# R401F.net
KiCad netlist of a schematic drawn in EAGLE
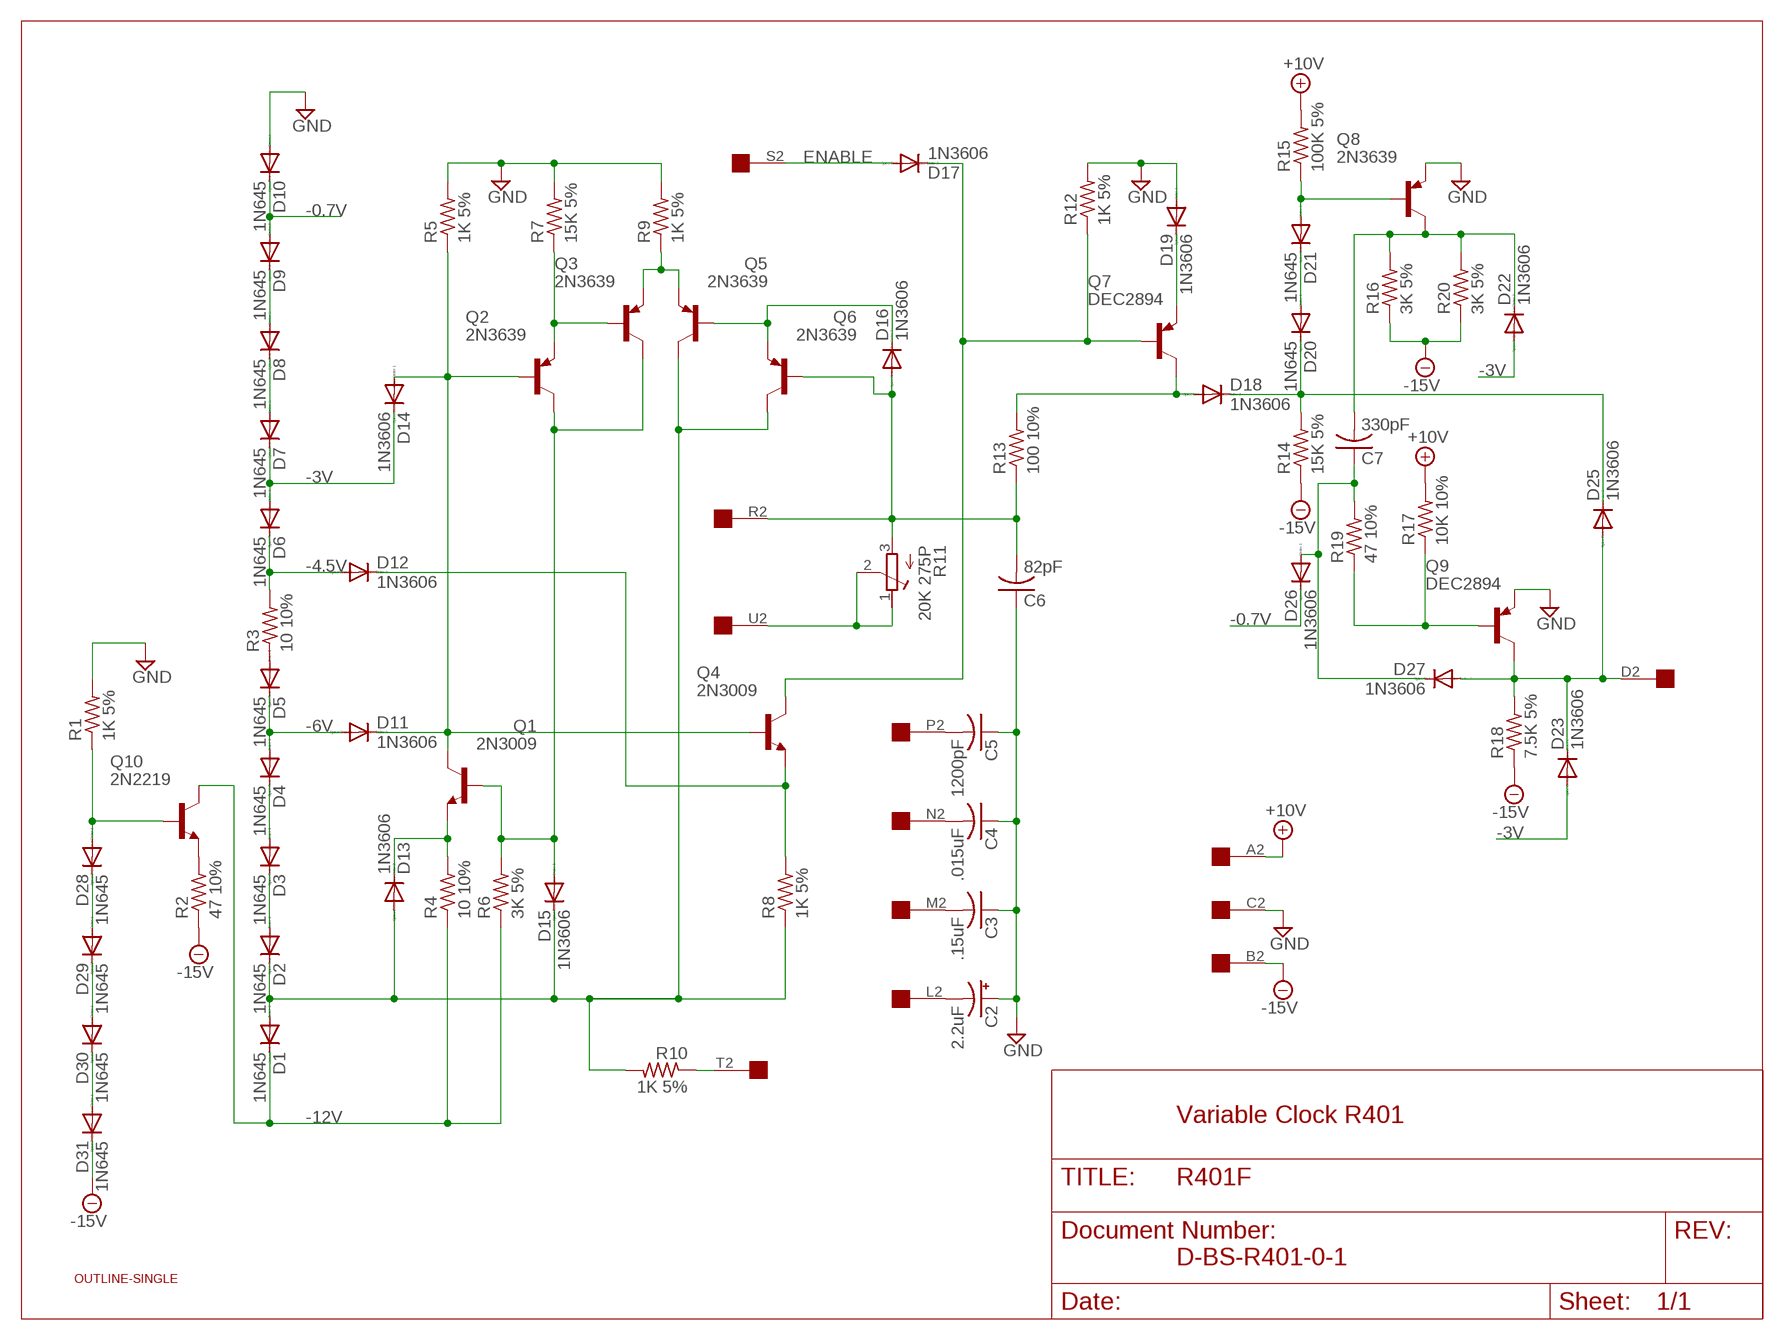
[diagram p0: schematic, sheet 1]

(export (version "E")
  (design (tool "Eeschema 10.0.6"))
  (components
    (comp (ref "C2")
      (value "2.2uF")
      (footprint "eagle-import:E12-4")
      (libsource (lib "eagle-import") (part "CPOL-USE12-4AXIAL"))
    )
    (comp (ref "C3")
      (value ".15uF")
      (footprint "eagle-import:C275-093X316")
      (libsource (lib "eagle-import") (part "C-US275-093X316"))
    )
    (comp (ref "C4")
      (value ".015uF")
      (footprint "eagle-import:C150-054X183")
      (libsource (lib "eagle-import") (part "C-US150-054X183"))
    )
    (comp (ref "C5")
      (value "1200pF")
      (footprint "eagle-import:C102-043X133")
      (libsource (lib "eagle-import") (part "C-US102-043X133"))
    )
    (comp (ref "C6")
      (value "82pF")
      (footprint "eagle-import:C150-054X183")
      (libsource (lib "eagle-import") (part "C-US150-054X183"))
    )
    (comp (ref "C7")
      (value "330pF")
      (footprint "eagle-import:C150-054X183")
      (libsource (lib "eagle-import") (part "C-US150-054X183"))
    )
    (comp (ref "D1")
      (value "1N645")
      (footprint "eagle-import:DO35-10")
      (libsource (lib "eagle-import") (part "1N4148DO35-10"))
    )
    (comp (ref "D2")
      (value "1N645")
      (footprint "eagle-import:DO35-10")
      (libsource (lib "eagle-import") (part "1N4148DO35-10"))
    )
    (comp (ref "D3")
      (value "1N645")
      (footprint "eagle-import:DO35-10")
      (libsource (lib "eagle-import") (part "1N4148DO35-10"))
    )
    (comp (ref "D4")
      (value "1N645")
      (footprint "eagle-import:DO35-10")
      (libsource (lib "eagle-import") (part "1N4148DO35-10"))
    )
    (comp (ref "D5")
      (value "1N645")
      (footprint "eagle-import:DO35-10")
      (libsource (lib "eagle-import") (part "1N4148DO35-10"))
    )
    (comp (ref "D6")
      (value "1N645")
      (footprint "eagle-import:DO35-10")
      (libsource (lib "eagle-import") (part "1N4148DO35-10"))
    )
    (comp (ref "D7")
      (value "1N645")
      (footprint "eagle-import:DO35-10")
      (libsource (lib "eagle-import") (part "1N4148DO35-10"))
    )
    (comp (ref "D8")
      (value "1N645")
      (footprint "eagle-import:DO35-10")
      (libsource (lib "eagle-import") (part "1N4148DO35-10"))
    )
    (comp (ref "D9")
      (value "1N645")
      (footprint "eagle-import:DO35-10")
      (libsource (lib "eagle-import") (part "1N4148DO35-10"))
    )
    (comp (ref "D10")
      (value "1N645")
      (footprint "eagle-import:DO35-10")
      (libsource (lib "eagle-import") (part "1N4148DO35-10"))
    )
    (comp (ref "D11")
      (value "1N3606")
      (footprint "eagle-import:DO35-10")
      (libsource (lib "eagle-import") (part "1N4148DO35-10"))
    )
    (comp (ref "D12")
      (value "1N3606")
      (footprint "eagle-import:DO35-10")
      (libsource (lib "eagle-import") (part "1N4148DO35-10"))
    )
    (comp (ref "D13")
      (value "1N3606")
      (footprint "eagle-import:DO35-10")
      (libsource (lib "eagle-import") (part "1N4148DO35-10"))
    )
    (comp (ref "D14")
      (value "1N3606")
      (footprint "eagle-import:DO35-10")
      (libsource (lib "eagle-import") (part "1N4148DO35-10"))
    )
    (comp (ref "D15")
      (value "1N3606")
      (footprint "eagle-import:DO35-10")
      (libsource (lib "eagle-import") (part "1N4148DO35-10"))
    )
    (comp (ref "D16")
      (value "1N3606")
      (footprint "eagle-import:DO35-10")
      (libsource (lib "eagle-import") (part "1N4148DO35-10"))
    )
    (comp (ref "D17")
      (value "1N3606")
      (footprint "eagle-import:DO35-10")
      (libsource (lib "eagle-import") (part "1N4148DO35-10"))
    )
    (comp (ref "D18")
      (value "1N3606")
      (footprint "eagle-import:DO35-10")
      (libsource (lib "eagle-import") (part "1N4148DO35-10"))
    )
    (comp (ref "D19")
      (value "1N3606")
      (footprint "eagle-import:DO35-10")
      (libsource (lib "eagle-import") (part "1N4148DO35-10"))
    )
    (comp (ref "D20")
      (value "1N645")
      (footprint "eagle-import:DO35-10")
      (libsource (lib "eagle-import") (part "1N4148DO35-10"))
    )
    (comp (ref "D21")
      (value "1N645")
      (footprint "eagle-import:DO35-10")
      (libsource (lib "eagle-import") (part "1N4148DO35-10"))
    )
    (comp (ref "D22")
      (value "1N3606")
      (footprint "eagle-import:DO35-10")
      (libsource (lib "eagle-import") (part "1N4148DO35-10"))
    )
    (comp (ref "D23")
      (value "1N3606")
      (footprint "eagle-import:DO35-10")
      (libsource (lib "eagle-import") (part "1N4148DO35-10"))
    )
    (comp (ref "D25")
      (value "1N3606")
      (footprint "eagle-import:DO35-10")
      (libsource (lib "eagle-import") (part "1N4148DO35-10"))
    )
    (comp (ref "D26")
      (value "1N3606")
      (footprint "eagle-import:DO35-10")
      (libsource (lib "eagle-import") (part "1N4148DO35-10"))
    )
    (comp (ref "D27")
      (value "1N3606")
      (footprint "eagle-import:DO35-10")
      (libsource (lib "eagle-import") (part "1N4148DO35-10"))
    )
    (comp (ref "D28")
      (value "1N645")
      (footprint "eagle-import:DO35-10")
      (libsource (lib "eagle-import") (part "1N4148DO35-10"))
    )
    (comp (ref "D29")
      (value "1N645")
      (footprint "eagle-import:DO35-10")
      (libsource (lib "eagle-import") (part "1N4148DO35-10"))
    )
    (comp (ref "D30")
      (value "1N645")
      (footprint "eagle-import:DO35-10")
      (libsource (lib "eagle-import") (part "1N4148DO35-10"))
    )
    (comp (ref "D31")
      (value "1N645")
      (footprint "eagle-import:DO35-10")
      (libsource (lib "eagle-import") (part "1N4148DO35-10"))
    )
    (comp (ref "Q1")
      (value "2N3009")
      (footprint "eagle-import:TO5")
      (libsource (lib "eagle-import") (part "2N2102"))
    )
    (comp (ref "Q2")
      (value "2N3639")
      (footprint "eagle-import:TO39")
      (libsource (lib "eagle-import") (part "2N2904"))
    )
    (comp (ref "Q3")
      (value "2N3639")
      (footprint "eagle-import:TO39")
      (libsource (lib "eagle-import") (part "2N2904"))
    )
    (comp (ref "Q4")
      (value "2N3009")
      (footprint "eagle-import:TO5")
      (libsource (lib "eagle-import") (part "2N2102"))
    )
    (comp (ref "Q5")
      (value "2N3639")
      (footprint "eagle-import:TO39")
      (libsource (lib "eagle-import") (part "2N2904"))
    )
    (comp (ref "Q6")
      (value "2N3639")
      (footprint "eagle-import:TO39")
      (libsource (lib "eagle-import") (part "2N2904"))
    )
    (comp (ref "Q7")
      (value "DEC2894")
      (footprint "eagle-import:TO39")
      (libsource (lib "eagle-import") (part "2N2904"))
    )
    (comp (ref "Q8")
      (value "2N3639")
      (footprint "eagle-import:TO39")
      (libsource (lib "eagle-import") (part "2N2904"))
    )
    (comp (ref "Q9")
      (value "DEC2894")
      (footprint "eagle-import:TO39")
      (libsource (lib "eagle-import") (part "2N2904"))
    )
    (comp (ref "Q10")
      (value "2N2219")
      (footprint "eagle-import:TO5")
      (libsource (lib "eagle-import") (part "2N2102"))
    )
    (comp (ref "R1")
      (value "1K 5%")
      (footprint "eagle-import:0207_10")
      (libsource (lib "eagle-import") (part "R-US_0207/10"))
    )
    (comp (ref "R2")
      (value "47 10%")
      (footprint "eagle-import:0207_10")
      (libsource (lib "eagle-import") (part "R-US_0207/10"))
    )
    (comp (ref "R3")
      (value "10 10%")
      (footprint "eagle-import:0207_10")
      (libsource (lib "eagle-import") (part "R-US_0207/10"))
    )
    (comp (ref "R4")
      (value "10 10%")
      (footprint "eagle-import:0207_10")
      (libsource (lib "eagle-import") (part "R-US_0207/10"))
    )
    (comp (ref "R5")
      (value "1K 5%")
      (footprint "eagle-import:0207_10")
      (libsource (lib "eagle-import") (part "R-US_0207/10"))
    )
    (comp (ref "R6")
      (value "3K 5%")
      (footprint "eagle-import:0207_10")
      (libsource (lib "eagle-import") (part "R-US_0207/10"))
    )
    (comp (ref "R7")
      (value "15K 5%")
      (footprint "eagle-import:0207_10")
      (libsource (lib "eagle-import") (part "R-US_0207/10"))
    )
    (comp (ref "R8")
      (value "1K 5%")
      (footprint "eagle-import:0207_10")
      (libsource (lib "eagle-import") (part "R-US_0207/10"))
    )
    (comp (ref "R9")
      (value "1K 5%")
      (footprint "eagle-import:0207_10")
      (libsource (lib "eagle-import") (part "R-US_0207/10"))
    )
    (comp (ref "R10")
      (value "1K 5%")
      (footprint "eagle-import:0207_10")
      (libsource (lib "eagle-import") (part "R-US_0207/10"))
    )
    (comp (ref "R11")
      (value "20K 275P")
      (footprint "eagle-import:3006Y")
      (libsource (lib "eagle-import") (part "275P"))
    )
    (comp (ref "R12")
      (value "1K 5%")
      (footprint "eagle-import:0207_10")
      (libsource (lib "eagle-import") (part "R-US_0207/10"))
    )
    (comp (ref "R13")
      (value "100 10%")
      (footprint "eagle-import:0207_10")
      (libsource (lib "eagle-import") (part "R-US_0207/10"))
    )
    (comp (ref "R14")
      (value "15K 5%")
      (footprint "eagle-import:0207_10")
      (libsource (lib "eagle-import") (part "R-US_0207/10"))
    )
    (comp (ref "R15")
      (value "100K 5%")
      (footprint "eagle-import:0207_10")
      (libsource (lib "eagle-import") (part "R-US_0207/10"))
    )
    (comp (ref "R16")
      (value "3K 5%")
      (footprint "eagle-import:0207_10")
      (libsource (lib "eagle-import") (part "R-US_0207/10"))
    )
    (comp (ref "R17")
      (value "10K 10%")
      (footprint "eagle-import:0207_10")
      (libsource (lib "eagle-import") (part "R-US_0207/10"))
    )
    (comp (ref "R18")
      (value "7.5K 5%")
      (footprint "eagle-import:0207_10")
      (libsource (lib "eagle-import") (part "R-US_0207/10"))
    )
    (comp (ref "R19")
      (value "47 10%")
      (footprint "eagle-import:0207_10")
      (libsource (lib "eagle-import") (part "R-US_0207/10"))
    )
    (comp (ref "R20")
      (value "3K 5%")
      (footprint "eagle-import:0207_10")
      (libsource (lib "eagle-import") (part "R-US_0207/10"))
    )
    (comp (ref "U$1")
      (value "OUTLINE-SINGLE")
      (footprint "eagle-import:SINGLE")
      (libsource (lib "eagle-import") (part "OUTLINE-SINGLE"))
    )
    (comp (ref "U$2")
      (value "EDGE-1")
      (footprint "eagle-import:EDGE-CON1")
      (libsource (lib "eagle-import") (part "EDGE-1"))
    )
  )
  (nets
    (net (code "1") (name "+10V") (class "Default")
      (node (ref "R15") (pin "2") (pinfunction "2_2") (pintype "passive"))
      (node (ref "R17") (pin "2") (pinfunction "2_2") (pintype "passive"))
      (node (ref "U$2") (pin "A2") (pinfunction "1_A2") (pintype "bidirectional"))
    )
    (net (code "2") (name "-15V") (class "Default")
      (node (ref "D31") (pin "C") (pinfunction "C_C") (pintype "passive"))
      (node (ref "R14") (pin "1") (pinfunction "1_1") (pintype "passive"))
      (node (ref "R16") (pin "1") (pinfunction "1_1") (pintype "passive"))
      (node (ref "R18") (pin "1") (pinfunction "1_1") (pintype "passive"))
      (node (ref "R2") (pin "1") (pinfunction "1_1") (pintype "passive"))
      (node (ref "R20") (pin "1") (pinfunction "1_1") (pintype "passive"))
      (node (ref "U$2") (pin "B2") (pinfunction "1_B2") (pintype "bidirectional"))
    )
    (net (code "3") (name "/-0.7V") (class "Default")
      (node (ref "D10") (pin "C") (pinfunction "C_C") (pintype "passive"))
      (node (ref "D26") (pin "C") (pinfunction "C_C") (pintype "passive"))
      (node (ref "D9") (pin "A") (pinfunction "A_A") (pintype "passive"))
    )
    (net (code "4") (name "/-3V") (class "Default")
      (node (ref "D14") (pin "C") (pinfunction "C_C") (pintype "passive"))
      (node (ref "D22") (pin "A") (pinfunction "A_A") (pintype "passive"))
      (node (ref "D23") (pin "A") (pinfunction "A_A") (pintype "passive"))
      (node (ref "D6") (pin "A") (pinfunction "A_A") (pintype "passive"))
      (node (ref "D7") (pin "C") (pinfunction "C_C") (pintype "passive"))
    )
    (net (code "5") (name "/-4.5V") (class "Default")
      (node (ref "D12") (pin "A") (pinfunction "A_A") (pintype "passive"))
      (node (ref "D6") (pin "C") (pinfunction "C_C") (pintype "passive"))
      (node (ref "R3") (pin "2") (pinfunction "2_2") (pintype "passive"))
    )
    (net (code "6") (name "/-6V") (class "Default")
      (node (ref "D11") (pin "A") (pinfunction "A_A") (pintype "passive"))
      (node (ref "D4") (pin "A") (pinfunction "A_A") (pintype "passive"))
      (node (ref "D5") (pin "C") (pinfunction "C_C") (pintype "passive"))
    )
    (net (code "7") (name "/-12V") (class "Default")
      (node (ref "D1") (pin "C") (pinfunction "C_C") (pintype "passive"))
      (node (ref "Q10") (pin "3") (pinfunction "C_3") (pintype "passive"))
      (node (ref "R4") (pin "1") (pinfunction "1_1") (pintype "passive"))
      (node (ref "R6") (pin "1") (pinfunction "1_1") (pintype "passive"))
    )
    (net (code "8") (name "/ENABLE") (class "Default")
      (node (ref "D17") (pin "A") (pinfunction "A_A") (pintype "passive"))
      (node (ref "U$2") (pin "S2") (pinfunction "1_S2") (pintype "bidirectional"))
    )
    (net (code "9") (name "GND") (class "Default")
      (node (ref "C2") (pin "+") (pinfunction "+_+") (pintype "passive"))
      (node (ref "C3") (pin "1") (pinfunction "1_1") (pintype "passive"))
      (node (ref "C4") (pin "1") (pinfunction "1_1") (pintype "passive"))
      (node (ref "C5") (pin "1") (pinfunction "1_1") (pintype "passive"))
      (node (ref "C6") (pin "1") (pinfunction "1_1") (pintype "passive"))
      (node (ref "D10") (pin "A") (pinfunction "A_A") (pintype "passive"))
      (node (ref "D19") (pin "A") (pinfunction "A_A") (pintype "passive"))
      (node (ref "Q8") (pin "1") (pinfunction "E_1") (pintype "passive"))
      (node (ref "Q9") (pin "1") (pinfunction "E_1") (pintype "passive"))
      (node (ref "R1") (pin "2") (pinfunction "2_2") (pintype "passive"))
      (node (ref "R12") (pin "2") (pinfunction "2_2") (pintype "passive"))
      (node (ref "R5") (pin "2") (pinfunction "2_2") (pintype "passive"))
      (node (ref "R7") (pin "2") (pinfunction "2_2") (pintype "passive"))
      (node (ref "R9") (pin "2") (pinfunction "2_2") (pintype "passive"))
      (node (ref "U$2") (pin "C2") (pinfunction "1_C2") (pintype "bidirectional"))
    )
    (net (code "10") (name "Net-(C7-Pad1)") (class "Default")
      (node (ref "C7") (pin "1") (pinfunction "1_1") (pintype "passive"))
      (node (ref "D26") (pin "A") (pinfunction "A_A") (pintype "passive"))
      (node (ref "D27") (pin "C") (pinfunction "C_C") (pintype "passive"))
      (node (ref "R19") (pin "2") (pinfunction "2_2") (pintype "passive"))
    )
    (net (code "11") (name "Net-(D2-PadA)") (class "Default")
      (node (ref "D2") (pin "A") (pinfunction "A_A") (pintype "passive"))
      (node (ref "D3") (pin "C") (pinfunction "C_C") (pintype "passive"))
    )
    (net (code "12") (name "Net-(D3-PadA)") (class "Default")
      (node (ref "D3") (pin "A") (pinfunction "A_A") (pintype "passive"))
      (node (ref "D4") (pin "C") (pinfunction "C_C") (pintype "passive"))
    )
    (net (code "13") (name "Net-(D5-PadA)") (class "Default")
      (node (ref "D5") (pin "A") (pinfunction "A_A") (pintype "passive"))
      (node (ref "R3") (pin "1") (pinfunction "1_1") (pintype "passive"))
    )
    (net (code "14") (name "Net-(D7-PadA)") (class "Default")
      (node (ref "D7") (pin "A") (pinfunction "A_A") (pintype "passive"))
      (node (ref "D8") (pin "C") (pinfunction "C_C") (pintype "passive"))
    )
    (net (code "15") (name "Net-(D8-PadA)") (class "Default")
      (node (ref "D8") (pin "A") (pinfunction "A_A") (pintype "passive"))
      (node (ref "D9") (pin "C") (pinfunction "C_C") (pintype "passive"))
    )
    (net (code "16") (name "Net-(D18-PadC)") (class "Default")
      (node (ref "D18") (pin "C") (pinfunction "C_C") (pintype "passive"))
      (node (ref "D20") (pin "C") (pinfunction "C_C") (pintype "passive"))
      (node (ref "D25") (pin "C") (pinfunction "C_C") (pintype "passive"))
      (node (ref "R14") (pin "2") (pinfunction "2_2") (pintype "passive"))
    )
    (net (code "17") (name "Net-(D20-PadA)") (class "Default")
      (node (ref "D20") (pin "A") (pinfunction "A_A") (pintype "passive"))
      (node (ref "D21") (pin "C") (pinfunction "C_C") (pintype "passive"))
    )
    (net (code "18") (name "Net-(D28-PadC)") (class "Default")
      (node (ref "D28") (pin "C") (pinfunction "C_C") (pintype "passive"))
      (node (ref "D29") (pin "A") (pinfunction "A_A") (pintype "passive"))
    )
    (net (code "19") (name "Net-(D29-PadC)") (class "Default")
      (node (ref "D29") (pin "C") (pinfunction "C_C") (pintype "passive"))
      (node (ref "D30") (pin "A") (pinfunction "A_A") (pintype "passive"))
    )
    (net (code "20") (name "Net-(D30-PadC)") (class "Default")
      (node (ref "D30") (pin "C") (pinfunction "C_C") (pintype "passive"))
      (node (ref "D31") (pin "A") (pinfunction "A_A") (pintype "passive"))
    )
    (net (code "21") (name "Net-(Q1-B)") (class "Default")
      (node (ref "D15") (pin "A") (pinfunction "A_A") (pintype "passive"))
      (node (ref "Q1") (pin "2") (pinfunction "B_2") (pintype "passive"))
      (node (ref "Q2") (pin "3") (pinfunction "C_3") (pintype "passive"))
      (node (ref "Q3") (pin "3") (pinfunction "C_3") (pintype "passive"))
      (node (ref "R6") (pin "2") (pinfunction "2_2") (pintype "passive"))
    )
    (net (code "22") (name "Net-(Q1-C)") (class "Default")
      (node (ref "D11") (pin "C") (pinfunction "C_C") (pintype "passive"))
      (node (ref "D14") (pin "A") (pinfunction "A_A") (pintype "passive"))
      (node (ref "Q1") (pin "3") (pinfunction "C_3") (pintype "passive"))
      (node (ref "Q2") (pin "2") (pinfunction "B_2") (pintype "passive"))
      (node (ref "Q4") (pin "2") (pinfunction "B_2") (pintype "passive"))
      (node (ref "R5") (pin "1") (pinfunction "1_1") (pintype "passive"))
    )
    (net (code "23") (name "Net-(Q1-E)") (class "Default")
      (node (ref "D13") (pin "C") (pinfunction "C_C") (pintype "passive"))
      (node (ref "Q1") (pin "1") (pinfunction "E_1") (pintype "passive"))
      (node (ref "R4") (pin "2") (pinfunction "2_2") (pintype "passive"))
    )
    (net (code "24") (name "Net-(Q2-E)") (class "Default")
      (node (ref "Q2") (pin "1") (pinfunction "E_1") (pintype "passive"))
      (node (ref "Q3") (pin "2") (pinfunction "B_2") (pintype "passive"))
      (node (ref "R7") (pin "1") (pinfunction "1_1") (pintype "passive"))
    )
    (net (code "25") (name "Net-(Q3-E)") (class "Default")
      (node (ref "Q3") (pin "1") (pinfunction "E_1") (pintype "passive"))
      (node (ref "Q5") (pin "1") (pinfunction "E_1") (pintype "passive"))
      (node (ref "R9") (pin "1") (pinfunction "1_1") (pintype "passive"))
    )
    (net (code "26") (name "Net-(Q4-C)") (class "Default")
      (node (ref "D17") (pin "C") (pinfunction "C_C") (pintype "passive"))
      (node (ref "Q4") (pin "3") (pinfunction "C_3") (pintype "passive"))
      (node (ref "Q7") (pin "2") (pinfunction "B_2") (pintype "passive"))
      (node (ref "R12") (pin "1") (pinfunction "1_1") (pintype "passive"))
    )
    (net (code "27") (name "Net-(Q4-E)") (class "Default")
      (node (ref "D12") (pin "C") (pinfunction "C_C") (pintype "passive"))
      (node (ref "Q4") (pin "1") (pinfunction "E_1") (pintype "passive"))
      (node (ref "R8") (pin "2") (pinfunction "2_2") (pintype "passive"))
    )
    (net (code "28") (name "Net-(Q5-B)") (class "Default")
      (node (ref "D16") (pin "C") (pinfunction "C_C") (pintype "passive"))
      (node (ref "Q5") (pin "2") (pinfunction "B_2") (pintype "passive"))
      (node (ref "Q6") (pin "1") (pinfunction "E_1") (pintype "passive"))
    )
    (net (code "29") (name "Net-(Q5-C)") (class "Default")
      (node (ref "D1") (pin "A") (pinfunction "A_A") (pintype "passive"))
      (node (ref "D13") (pin "A") (pinfunction "A_A") (pintype "passive"))
      (node (ref "D15") (pin "C") (pinfunction "C_C") (pintype "passive"))
      (node (ref "D2") (pin "C") (pinfunction "C_C") (pintype "passive"))
      (node (ref "Q5") (pin "3") (pinfunction "C_3") (pintype "passive"))
      (node (ref "Q6") (pin "3") (pinfunction "C_3") (pintype "passive"))
      (node (ref "R10") (pin "2") (pinfunction "2_2") (pintype "passive"))
      (node (ref "R8") (pin "1") (pinfunction "1_1") (pintype "passive"))
    )
    (net (code "30") (name "Net-(Q6-B)") (class "Default")
      (node (ref "C6") (pin "2") (pinfunction "2_2") (pintype "passive"))
      (node (ref "D16") (pin "A") (pinfunction "A_A") (pintype "passive"))
      (node (ref "Q6") (pin "2") (pinfunction "B_2") (pintype "passive"))
      (node (ref "R11") (pin "3") (pinfunction "E_3") (pintype "passive"))
      (node (ref "R13") (pin "1") (pinfunction "1_1") (pintype "passive"))
      (node (ref "U$2") (pin "R2") (pinfunction "1_R2") (pintype "bidirectional"))
    )
    (net (code "31") (name "Net-(Q7-C)") (class "Default")
      (node (ref "D18") (pin "A") (pinfunction "A_A") (pintype "passive"))
      (node (ref "Q7") (pin "3") (pinfunction "C_3") (pintype "passive"))
      (node (ref "R13") (pin "2") (pinfunction "2_2") (pintype "passive"))
    )
    (net (code "32") (name "Net-(Q7-E)") (class "Default")
      (node (ref "D19") (pin "C") (pinfunction "C_C") (pintype "passive"))
      (node (ref "Q7") (pin "1") (pinfunction "E_1") (pintype "passive"))
    )
    (net (code "33") (name "Net-(Q8-B)") (class "Default")
      (node (ref "D21") (pin "A") (pinfunction "A_A") (pintype "passive"))
      (node (ref "Q8") (pin "2") (pinfunction "B_2") (pintype "passive"))
      (node (ref "R15") (pin "1") (pinfunction "1_1") (pintype "passive"))
    )
    (net (code "34") (name "Net-(Q8-C)") (class "Default")
      (node (ref "C7") (pin "2") (pinfunction "2_2") (pintype "passive"))
      (node (ref "D22") (pin "C") (pinfunction "C_C") (pintype "passive"))
      (node (ref "Q8") (pin "3") (pinfunction "C_3") (pintype "passive"))
      (node (ref "R16") (pin "2") (pinfunction "2_2") (pintype "passive"))
      (node (ref "R20") (pin "2") (pinfunction "2_2") (pintype "passive"))
    )
    (net (code "35") (name "Net-(Q9-B)") (class "Default")
      (node (ref "Q9") (pin "2") (pinfunction "B_2") (pintype "passive"))
      (node (ref "R17") (pin "1") (pinfunction "1_1") (pintype "passive"))
      (node (ref "R19") (pin "1") (pinfunction "1_1") (pintype "passive"))
    )
    (net (code "36") (name "Net-(Q9-C)") (class "Default")
      (node (ref "D23") (pin "C") (pinfunction "C_C") (pintype "passive"))
      (node (ref "D25") (pin "A") (pinfunction "A_A") (pintype "passive"))
      (node (ref "D27") (pin "A") (pinfunction "A_A") (pintype "passive"))
      (node (ref "Q9") (pin "3") (pinfunction "C_3") (pintype "passive"))
      (node (ref "R18") (pin "2") (pinfunction "2_2") (pintype "passive"))
      (node (ref "U$2") (pin "D2") (pinfunction "1_D2") (pintype "bidirectional"))
    )
    (net (code "37") (name "Net-(Q10-B)") (class "Default")
      (node (ref "D28") (pin "A") (pinfunction "A_A") (pintype "passive"))
      (node (ref "Q10") (pin "2") (pinfunction "B_2") (pintype "passive"))
      (node (ref "R1") (pin "1") (pinfunction "1_1") (pintype "passive"))
    )
    (net (code "38") (name "Net-(Q10-E)") (class "Default")
      (node (ref "Q10") (pin "1") (pinfunction "E_1") (pintype "passive"))
      (node (ref "R2") (pin "2") (pinfunction "2_2") (pintype "passive"))
    )
    (net (code "39") (name "Net-(R11-A)") (class "Default")
      (node (ref "R11") (pin "1") (pinfunction "A_1") (pintype "passive"))
      (node (ref "R11") (pin "2") (pinfunction "S_2") (pintype "passive"))
      (node (ref "U$2") (pin "U2") (pinfunction "1_U2") (pintype "bidirectional"))
    )
    (net (code "40") (name "Net-(U$2J-1)") (class "Default")
      (node (ref "C2") (pin "-") (pinfunction "-_-") (pintype "passive"))
      (node (ref "U$2") (pin "L2") (pinfunction "1_L2") (pintype "bidirectional"))
    )
    (net (code "41") (name "Net-(U$2K-1)") (class "Default")
      (node (ref "C3") (pin "2") (pinfunction "2_2") (pintype "passive"))
      (node (ref "U$2") (pin "M2") (pinfunction "1_M2") (pintype "bidirectional"))
    )
    (net (code "42") (name "Net-(U$2L-1)") (class "Default")
      (node (ref "C4") (pin "2") (pinfunction "2_2") (pintype "passive"))
      (node (ref "U$2") (pin "N2") (pinfunction "1_N2") (pintype "bidirectional"))
    )
    (net (code "43") (name "Net-(U$2M-1)") (class "Default")
      (node (ref "C5") (pin "2") (pinfunction "2_2") (pintype "passive"))
      (node (ref "U$2") (pin "P2") (pinfunction "1_P2") (pintype "bidirectional"))
    )
    (net (code "44") (name "Net-(U$2P-1)") (class "Default")
      (node (ref "R10") (pin "1") (pinfunction "1_1") (pintype "passive"))
      (node (ref "U$2") (pin "T2") (pinfunction "1_T2") (pintype "bidirectional"))
    )
  )
)
